# LM-008.net
KiCad netlist of a schematic drawn in Altium Designer
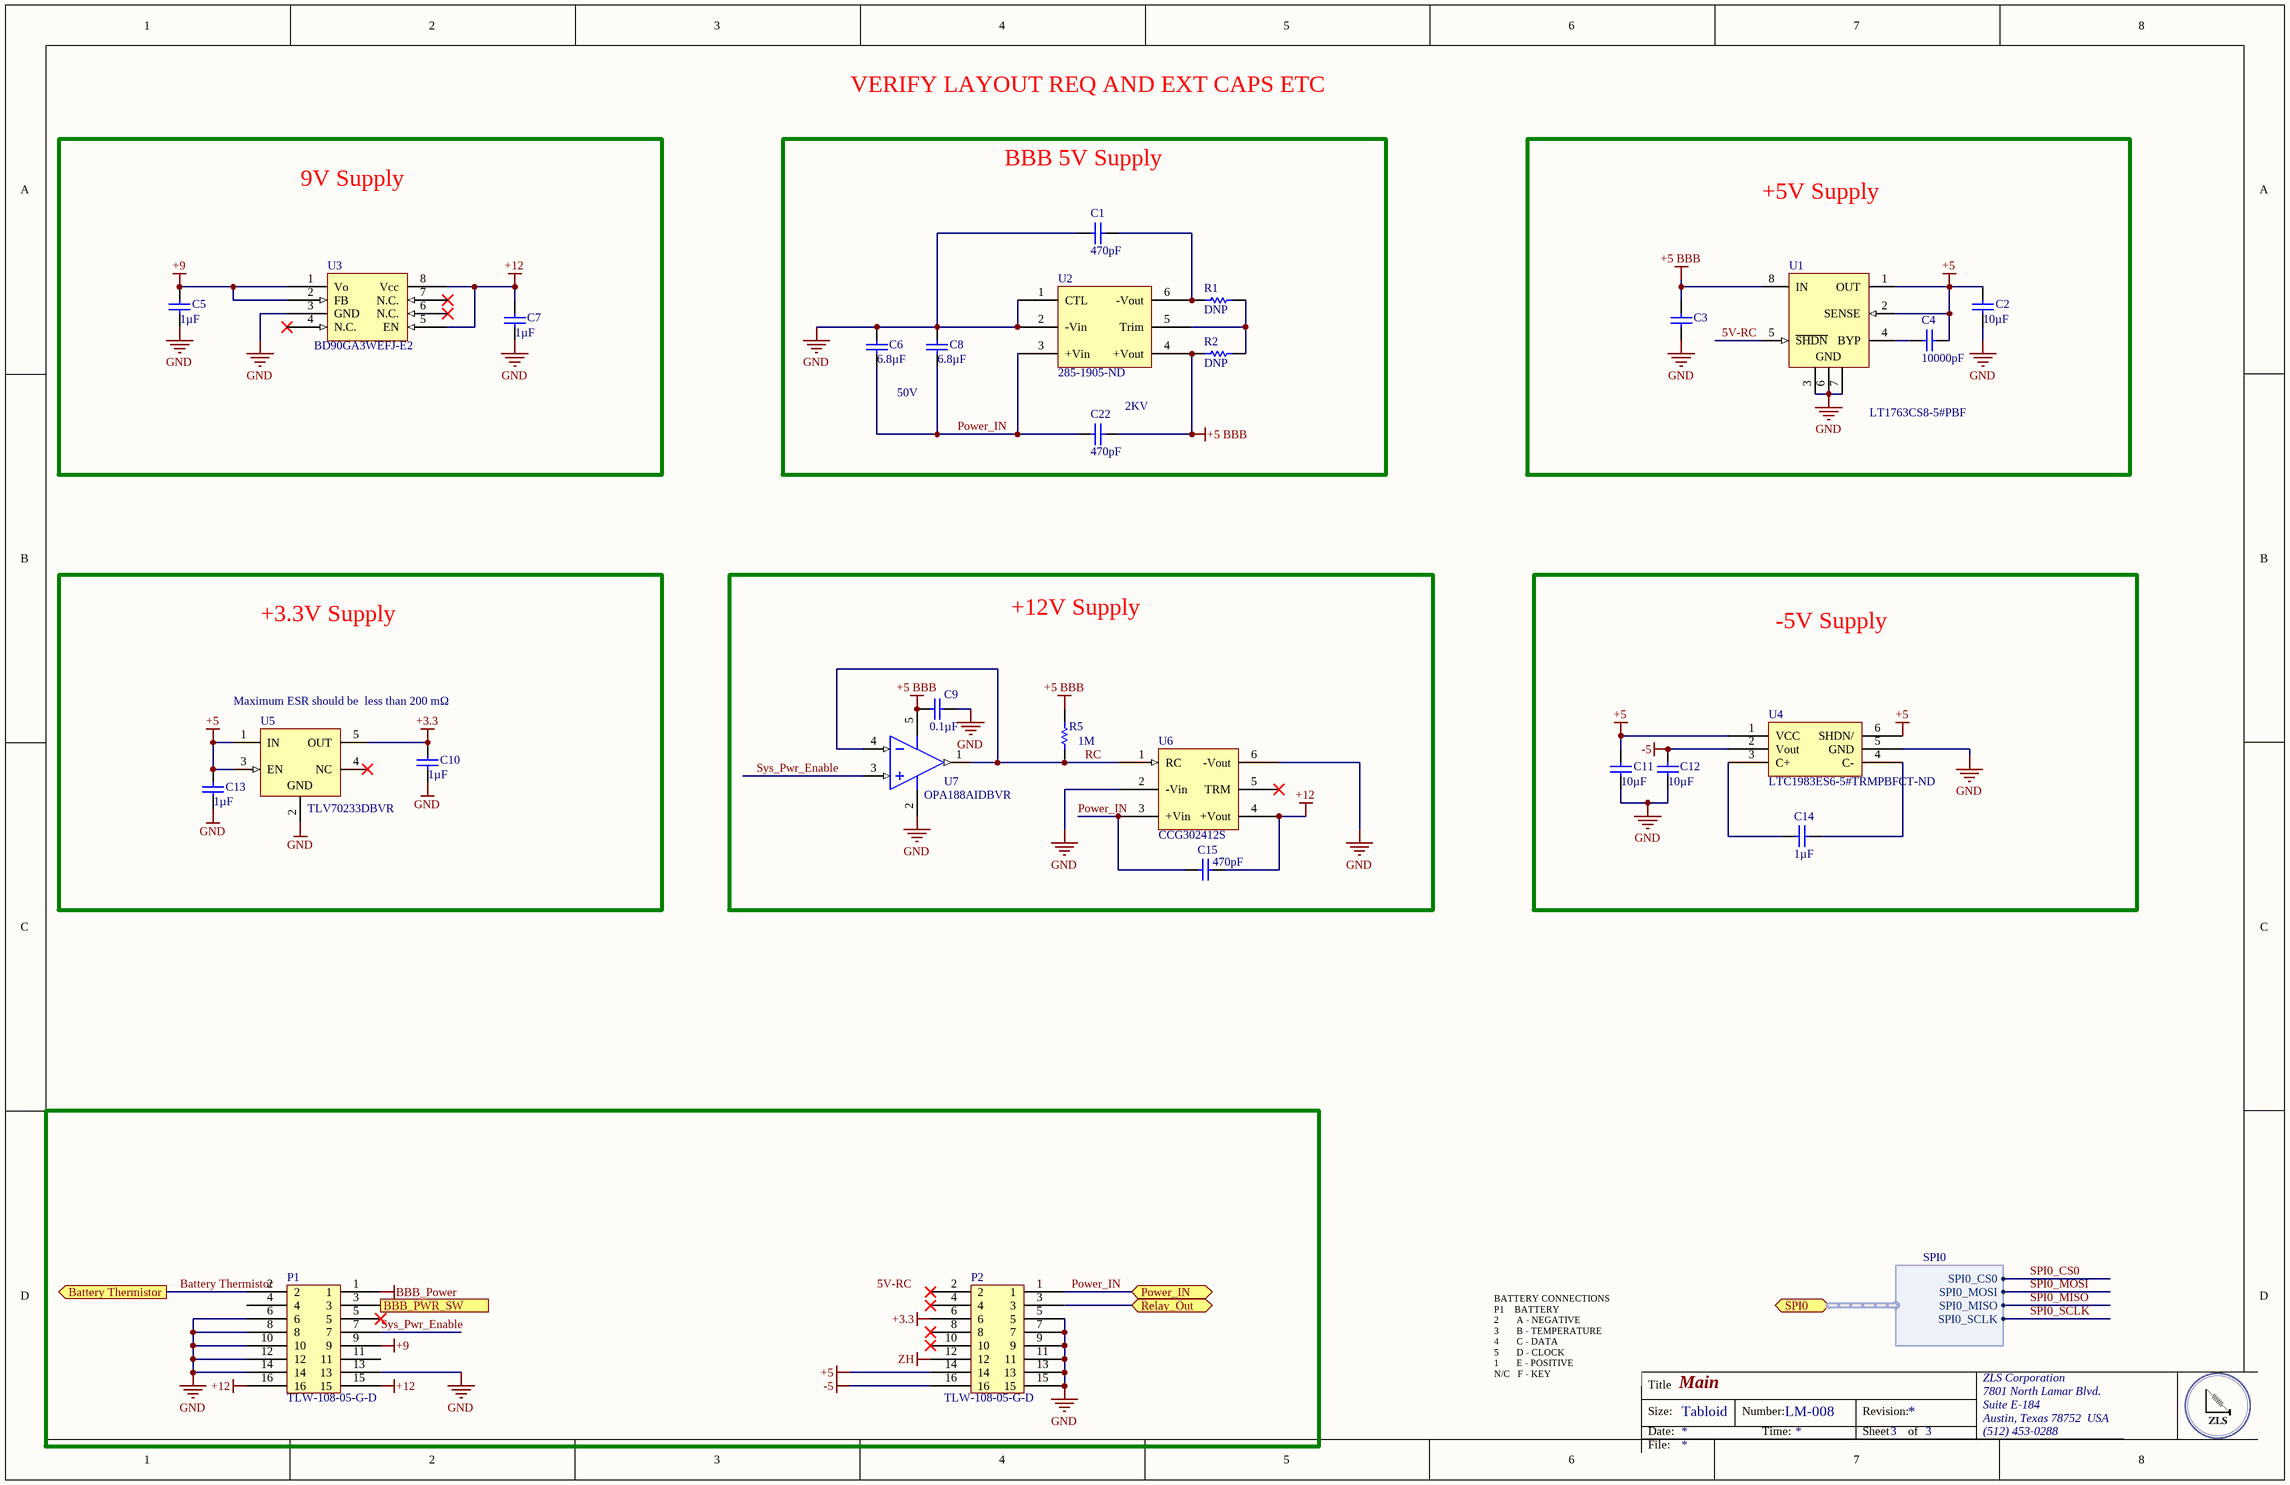
[diagram p0: LM-008.SchDoc]

(export (version "E")
  (design (tool "Eeschema 10.0.6"))
  (components
    (comp (ref "C1")
      (value "CAP CER 1UF 50V X7R 1210")
      (footprint "CAPC1206(3216)130_N")
      (fields
        (field (name "MANUFACTURER") "Murata Electronics North America")
        (field (name "MANUFACTURER PART NUMBER") "GRM32RR71H105KA01L")
        (field (name "CAPACITANCE") "470pF")
        (field (name "TOLERANCE") "±10%")
      )
      (libsource (lib "Altium Content Vault") (part "CMP-1037-04913-1"))
    )
    (comp (ref "C2")
      (value "CAP CER 1UF 50V X7R 1210")
      (footprint "CAPC1206(3216)130_N")
      (fields
        (field (name "MANUFACTURER") "Murata Electronics North America")
        (field (name "MANUFACTURER PART NUMBER") "GRM32RR71H105KA01L")
        (field (name "CAPACITANCE") "10µF")
        (field (name "TOLERANCE") "±10%")
      )
      (libsource (lib "Altium Content Vault") (part "CMP-1037-04913-1"))
    )
    (comp (ref "C3")
      (value "1uF")
      (footprint "CAPC1206(3216)130_N")
      (libsource (lib "Altium Content Vault") (part "CMP-1037-04913-1"))
    )
    (comp (ref "C4")
      (value "CAP CER 1UF 50V X7R 1210")
      (footprint "CAPC1206(3216)130_N")
      (fields
        (field (name "MANUFACTURER") "Murata Electronics North America")
        (field (name "MANUFACTURER PART NUMBER") "GRM32RR71H105KA01L")
        (field (name "CAPACITANCE") "10000pF")
        (field (name "TOLERANCE") "±10%")
      )
      (libsource (lib "Altium Content Vault") (part "CMP-1037-04913-1"))
    )
    (comp (ref "C5")
      (value "CAP CER 1UF 50V X7R 1210")
      (footprint "CAPC1206(3216)130_N")
      (fields
        (field (name "MANUFACTURER") "Murata Electronics North America")
        (field (name "MANUFACTURER PART NUMBER") "GRM32RR71H105KA01L")
        (field (name "CAPACITANCE") "1µF")
        (field (name "TOLERANCE") "±10%")
      )
      (libsource (lib "Altium Content Vault") (part "CMP-1037-04913-1"))
    )
    (comp (ref "C6")
      (value "CAP CER 1UF 50V X7R 1210")
      (footprint "CAPC1206(3216)130_N")
      (fields
        (field (name "MANUFACTURER") "Murata Electronics North America")
        (field (name "MANUFACTURER PART NUMBER") "GRM32RR71H105KA01L")
        (field (name "CAPACITANCE") "6.8µF")
        (field (name "TOLERANCE") "±10%")
      )
      (libsource (lib "Altium Content Vault") (part "CMP-1037-04913-1"))
    )
    (comp (ref "C7")
      (value "CAP CER 1UF 50V X7R 1210")
      (footprint "CAPC1206(3216)130_N")
      (fields
        (field (name "MANUFACTURER") "Murata Electronics North America")
        (field (name "MANUFACTURER PART NUMBER") "GRM32RR71H105KA01L")
        (field (name "CAPACITANCE") "1µF")
        (field (name "TOLERANCE") "±10%")
      )
      (libsource (lib "Altium Content Vault") (part "CMP-1037-04913-1"))
    )
    (comp (ref "C8")
      (value "CAP CER 1UF 50V X7R 1210")
      (footprint "CAPC1206(3216)130_N")
      (fields
        (field (name "MANUFACTURER") "Murata Electronics North America")
        (field (name "MANUFACTURER PART NUMBER") "GRM32RR71H105KA01L")
        (field (name "CAPACITANCE") "6.8µF")
        (field (name "TOLERANCE") "±10%")
      )
      (libsource (lib "Altium Content Vault") (part "CMP-1037-04913-1"))
    )
    (comp (ref "C9")
      (value "CAP CER 0.1UF 16V X7R 0805")
      (footprint "CAPC0805(2012)145_N")
      (fields
        (field (name "TOLERANCE") "±10%")
        (field (name "MANUFACTURER") "Murata Electronics North America")
        (field (name "MANUFACTURER PART NUMBER") "GRM219R71C104KA01D")
        (field (name "CAPACITANCE") "0.1µF")
      )
      (libsource (lib "Altium Content Vault") (part "CMP-1036-04795-1"))
    )
    (comp (ref "C10")
      (value "CAP CER 1UF 50V X7R 1210")
      (footprint "CAPC1206(3216)130_N")
      (fields
        (field (name "MANUFACTURER") "Murata Electronics North America")
        (field (name "MANUFACTURER PART NUMBER") "GRM32RR71H105KA01L")
        (field (name "CAPACITANCE") "1µF")
        (field (name "TOLERANCE") "±10%")
      )
      (libsource (lib "Altium Content Vault") (part "CMP-1037-04913-1"))
    )
    (comp (ref "C11")
      (value "CAP CER 1UF 50V X7R 1210")
      (footprint "CAPC1206(3216)130_N")
      (fields
        (field (name "MANUFACTURER") "Murata Electronics North America")
        (field (name "MANUFACTURER PART NUMBER") "GRM32RR71H105KA01L")
        (field (name "CAPACITANCE") "10µF")
        (field (name "TOLERANCE") "±10%")
      )
      (libsource (lib "Altium Content Vault") (part "CMP-1037-04913-1"))
    )
    (comp (ref "C12")
      (value "CAP CER 1UF 50V X7R 1210")
      (footprint "CAPC1206(3216)130_N")
      (fields
        (field (name "MANUFACTURER") "Murata Electronics North America")
        (field (name "MANUFACTURER PART NUMBER") "GRM32RR71H105KA01L")
        (field (name "CAPACITANCE") "10µF")
        (field (name "TOLERANCE") "±10%")
      )
      (libsource (lib "Altium Content Vault") (part "CMP-1037-04913-1"))
    )
    (comp (ref "C13")
      (value "CAP CER 1UF 50V X7R 1210")
      (footprint "CAPC1206(3216)130_N")
      (fields
        (field (name "MANUFACTURER") "Murata Electronics North America")
        (field (name "MANUFACTURER PART NUMBER") "GRM32RR71H105KA01L")
        (field (name "CAPACITANCE") "1µF")
        (field (name "TOLERANCE") "±10%")
      )
      (libsource (lib "Altium Content Vault") (part "CMP-1037-04913-1"))
    )
    (comp (ref "C14")
      (value "CAP CER 1UF 50V X7R 1210")
      (footprint "CAPC1206(3216)130_N")
      (fields
        (field (name "MANUFACTURER") "Murata Electronics North America")
        (field (name "MANUFACTURER PART NUMBER") "GRM32RR71H105KA01L")
        (field (name "CAPACITANCE") "1µF")
        (field (name "TOLERANCE") "±10%")
      )
      (libsource (lib "Altium Content Vault") (part "CMP-1037-04913-1"))
    )
    (comp (ref "C15")
      (value "CAP CER 470PF 3KV X7R 1812")
      (footprint "CAPC1812(4532)230_M")
      (fields
        (field (name "MANUFACTURER") "Kemet")
        (field (name "MANUFACTURER PART NUMBER") "C1812C471KHRACTU")
        (field (name "CAPACITANCE") "470pF")
        (field (name "TOLERANCE") "10%")
      )
      (libsource (lib "Altium Content Vault") (part "CMP-1040-00561-1"))
    )
    (comp (ref "C22")
      (value "CAP CER 1UF 50V X7R 1210")
      (footprint "CAPC1206(3216)130_N")
      (fields
        (field (name "MANUFACTURER") "Murata Electronics North America")
        (field (name "MANUFACTURER PART NUMBER") "GRM32RR71H105KA01L")
        (field (name "CAPACITANCE") "470pF")
        (field (name "TOLERANCE") "±10%")
      )
      (libsource (lib "Altium Content Vault") (part "CMP-1037-04913-1"))
    )
    (comp (ref "P1")
      (value "TLW-108-05-G-D")
      (footprint "TLW-108-05-G-D")
      (description "CONN HEADER .100\" 16POS DL GOLD")
      (fields
        (field (name "MANUFACTURER") "Samtec Inc.")
        (field (name "MANUFACTURER PART NUMBER") "TLW-108-05-G-D")
      )
      (libsource (lib "ZLS_Schematic_lib") (part "TLW-108-05-G-D"))
    )
    (comp (ref "P2")
      (value "TLW-108-05-G-D")
      (footprint "TLW-108-05-G-D")
      (description "CONN HEADER .100\" 16POS DL GOLD")
      (fields
        (field (name "MANUFACTURER") "Samtec Inc.")
        (field (name "MANUFACTURER PART NUMBER") "TLW-108-05-G-D")
      )
      (libsource (lib "ZLS_Schematic_lib") (part "TLW-108-05-G-D"))
    )
    (comp (ref "R1")
      (value "DNP")
      (footprint "RESC0402(1005)_L")
      (description "TBD")
      (libsource (lib "Altium Content Vault") (part "CMP-1011-00927-1"))
    )
    (comp (ref "R2")
      (value "DNP")
      (footprint "RESC0402(1005)_L")
      (description "TBD")
      (libsource (lib "Altium Content Vault") (part "CMP-1011-00927-1"))
    )
    (comp (ref "R5")
      (value "1M")
      (footprint "RESC0402(1005)_L")
      (fields (field (name "TOLERANCE") "±1%"))
      (libsource (lib "Altium Content Vault") (part "CMP-1011-00927-1"))
    )
    (comp (ref "U1")
      (value "LT1763CS8-5#PBF")
      (footprint "LT-S8-8_L")
      (fields (field (name "MANUFACTURER") "Linear Technology"))
      (libsource (lib "Altium Content Vault") (part "LT-LT1763-S8-8"))
    )
    (comp (ref "U2")
      (value "PXB15-24WS05/NT")
      (footprint "PXB15-24WS05/NT")
      (fields (field (name "SUPPLIER PART NUMBER 1") "285-1905-ND"))
      (libsource (lib "ZLS_Schematic_lib") (part "PXB15-24WS05/NT"))
    )
    (comp (ref "U3")
      (value "BD90GA3WEFJ-E2")
      (footprint "TSOP127P600X100-8N")
      (description "IC REG LDO 9V 0.3A 8HTSOP-J")
      (fields
        (field (name "MANUFACTURER") "Rohm Semiconductor")
        (field (name "MANUFACTURER PART NUMBER") "BD90GA3WEFJ-E2")
      )
      (libsource (lib "ZLS_Schematic_lib") (part "BD90GA3WEFJ-E2"))
    )
    (comp (ref "U4")
      (value "LTC1983ES6-5#TRMPBF")
      (footprint "SOT95P323X100-6N")
      (fields
        (field (name "SUPPLIER PART NUMBER 1") "LTC1983ES6-5#TRMPBFCT-ND")
        (field (name "MANUFACTURER") "Linear Technology/Analog Devices")
        (field (name "BASE PART NUMBER") "LTC1983-5")
      )
      (libsource (lib "ZLS_Schematic_lib") (part "LTC1983ES6-5#TRMPBF"))
    )
    (comp (ref "U5")
      (value "TLV70233DBVR")
      (footprint "DBV0005A_N")
      (fields (field (name "MANUFACTURER") "Texas Instruments"))
      (libsource (lib "Altium Content Vault") (part "TI-TXX7XXXX-5"))
    )
    (comp (ref "U6")
      (value "CCG302412S")
      (footprint "CCG30")
      (description "DC/DC CONVERTER 12V 2.5A PCB")
      (libsource (lib "ZLS_LIB") (part "CCG302412S"))
    )
    (comp (ref "U7")
      (value "OPA188AIDBVR")
      (footprint "DBV0005A_M")
      (fields (field (name "MANUFACTURER") "Texas Instruments"))
      (libsource (lib "Altium Content Vault") (part "CMP-0809-00005-2"))
    )
  )
  (nets
    (net (code "2") (name "+3.3") (class "Default")
      (node (ref "C10") (pin "2") (pinfunction "2_2") (pintype "passive"))
      (node (ref "P2") (pin "6") (pinfunction "6_6") (pintype "passive"))
      (node (ref "U5") (pin "5") (pinfunction "OUT_5") (pintype "power_in"))
    )
    (net (code "3") (name "+5") (class "Default")
      (node (ref "C11") (pin "2") (pinfunction "2_2") (pintype "passive"))
      (node (ref "C13") (pin "2") (pinfunction "2_2") (pintype "passive"))
      (node (ref "C2") (pin "2") (pinfunction "2_2") (pintype "passive"))
      (node (ref "C4") (pin "1") (pinfunction "1_1") (pintype "passive"))
      (node (ref "P2") (pin "14") (pinfunction "14_14") (pintype "passive"))
      (node (ref "U1") (pin "1") (pinfunction "OUT_1") (pintype "power_in"))
      (node (ref "U1") (pin "2") (pinfunction "SENSE_2") (pintype "input"))
      (node (ref "U4") (pin "1") (pinfunction "VCC_1") (pintype "passive"))
      (node (ref "U4") (pin "6") (pinfunction "SHDN/_6") (pintype "passive"))
      (node (ref "U5") (pin "1") (pinfunction "IN_1") (pintype "power_in"))
      (node (ref "U5") (pin "3") (pinfunction "EN_3") (pintype "input"))
    )
    (net (code "4") (name "+5 BBB") (class "Default")
      (node (ref "C22") (pin "1") (pinfunction "1_1") (pintype "passive"))
      (node (ref "C3") (pin "2") (pinfunction "2_2") (pintype "passive"))
      (node (ref "C9") (pin "1") (pinfunction "1_1") (pintype "passive"))
      (node (ref "R2") (pin "2") (pinfunction "2_2") (pintype "passive"))
      (node (ref "R5") (pin "2") (pinfunction "2_2") (pintype "passive"))
      (node (ref "U1") (pin "8") (pinfunction "IN_8") (pintype "power_in"))
      (node (ref "U2") (pin "4") (pinfunction "+Vout_4") (pintype "passive"))
      (node (ref "U7") (pin "5") (pinfunction "V+_5") (pintype "power_in"))
    )
    (net (code "5") (name "+9") (class "Default")
      (node (ref "C5") (pin "2") (pinfunction "2_2") (pintype "passive"))
      (node (ref "P1") (pin "9") (pinfunction "9_9") (pintype "passive"))
      (node (ref "U3") (pin "1") (pinfunction "Vo_1") (pintype "power_in"))
      (node (ref "U3") (pin "2") (pinfunction "FB_2") (pintype "input"))
    )
    (net (code "6") (name "+12") (class "Default")
      (node (ref "C15") (pin "2") (pinfunction "2_2") (pintype "passive"))
      (node (ref "C7") (pin "2") (pinfunction "2_2") (pintype "passive"))
      (node (ref "P1") (pin "15") (pinfunction "15_15") (pintype "passive"))
      (node (ref "P1") (pin "16") (pinfunction "16_16") (pintype "passive"))
      (node (ref "U3") (pin "5") (pinfunction "EN_5") (pintype "input"))
      (node (ref "U3") (pin "8") (pinfunction "Vcc_8") (pintype "power_in"))
      (node (ref "U6") (pin "4") (pinfunction "+Vout_4") (pintype "power_in"))
    )
    (net (code "7") (name "-5") (class "Default")
      (node (ref "C12") (pin "2") (pinfunction "2_2") (pintype "passive"))
      (node (ref "P2") (pin "16") (pinfunction "16_16") (pintype "passive"))
      (node (ref "U4") (pin "2") (pinfunction "Vout_2") (pintype "passive"))
    )
    (net (code "8") (name "/5V-RC") (class "Default")
      (node (ref "U1") (pin "5") (pinfunction "~{SHDN}_5") (pintype "input"))
    )
    (net (code "9") (name "/BBB_PWR_SW") (class "Default")
      (node (ref "P1") (pin "3") (pinfunction "3_3") (pintype "passive"))
    )
    (net (code "10") (name "/Battery Thermistor") (class "Default")
      (node (ref "P1") (pin "2") (pinfunction "2_2") (pintype "passive"))
    )
    (net (code "11") (name "/Power_IN") (class "Default")
      (node (ref "C15") (pin "1") (pinfunction "1_1") (pintype "passive"))
      (node (ref "C22") (pin "2") (pinfunction "2_2") (pintype "passive"))
      (node (ref "C6") (pin "1") (pinfunction "1_1") (pintype "passive"))
      (node (ref "C8") (pin "1") (pinfunction "1_1") (pintype "passive"))
      (node (ref "P2") (pin "1") (pinfunction "1_1") (pintype "passive"))
      (node (ref "U2") (pin "3") (pinfunction "+Vin_3") (pintype "passive"))
      (node (ref "U6") (pin "3") (pinfunction "+Vin_3") (pintype "passive"))
    )
    (net (code "12") (name "/RC") (class "Default")
      (node (ref "R5") (pin "1") (pinfunction "1_1") (pintype "passive"))
      (node (ref "U6") (pin "1") (pinfunction "RC_1") (pintype "input"))
      (node (ref "U7") (pin "1") (pinfunction "OUT_1") (pintype "output"))
      (node (ref "U7") (pin "4") (pinfunction "IN-_4") (pintype "input"))
    )
    (net (code "13") (name "/Relay_Out") (class "Default")
      (node (ref "P2") (pin "3") (pinfunction "3_3") (pintype "passive"))
    )
    (net (code "18") (name "/Sys_Pwr_Enable") (class "Default")
      (node (ref "P1") (pin "7") (pinfunction "7_7") (pintype "passive"))
      (node (ref "U7") (pin "3") (pinfunction "IN+_3") (pintype "input"))
    )
    (net (code "20") (name "BBB_Power") (class "Default")
      (node (ref "P1") (pin "1") (pinfunction "1_1") (pintype "passive"))
    )
    (net (code "21") (name "GND") (class "Default")
      (node (ref "C1") (pin "2") (pinfunction "2_2") (pintype "passive"))
      (node (ref "C10") (pin "1") (pinfunction "1_1") (pintype "passive"))
      (node (ref "C11") (pin "1") (pinfunction "1_1") (pintype "passive"))
      (node (ref "C12") (pin "1") (pinfunction "1_1") (pintype "passive"))
      (node (ref "C13") (pin "1") (pinfunction "1_1") (pintype "passive"))
      (node (ref "C2") (pin "1") (pinfunction "1_1") (pintype "passive"))
      (node (ref "C3") (pin "1") (pinfunction "1_1") (pintype "passive"))
      (node (ref "C5") (pin "1") (pinfunction "1_1") (pintype "passive"))
      (node (ref "C6") (pin "2") (pinfunction "2_2") (pintype "passive"))
      (node (ref "C7") (pin "1") (pinfunction "1_1") (pintype "passive"))
      (node (ref "C8") (pin "2") (pinfunction "2_2") (pintype "passive"))
      (node (ref "C9") (pin "2") (pinfunction "2_2") (pintype "passive"))
      (node (ref "P1") (pin "10") (pinfunction "10_10") (pintype "passive"))
      (node (ref "P1") (pin "12") (pinfunction "12_12") (pintype "passive"))
      (node (ref "P1") (pin "13") (pinfunction "13_13") (pintype "passive"))
      (node (ref "P1") (pin "14") (pinfunction "14_14") (pintype "passive"))
      (node (ref "P1") (pin "6") (pinfunction "6_6") (pintype "passive"))
      (node (ref "P1") (pin "8") (pinfunction "8_8") (pintype "passive"))
      (node (ref "P2") (pin "11") (pinfunction "11_11") (pintype "passive"))
      (node (ref "P2") (pin "13") (pinfunction "13_13") (pintype "passive"))
      (node (ref "P2") (pin "15") (pinfunction "15_15") (pintype "passive"))
      (node (ref "P2") (pin "5") (pinfunction "5_5") (pintype "passive"))
      (node (ref "P2") (pin "7") (pinfunction "7_7") (pintype "passive"))
      (node (ref "P2") (pin "9") (pinfunction "9_9") (pintype "passive"))
      (node (ref "U1") (pin "3") (pinfunction "GND_3") (pintype "power_in"))
      (node (ref "U1") (pin "6") (pinfunction "GND_6") (pintype "power_in"))
      (node (ref "U1") (pin "7") (pinfunction "GND_7") (pintype "power_in"))
      (node (ref "U2") (pin "1") (pinfunction "CTL_1") (pintype "passive"))
      (node (ref "U2") (pin "2") (pinfunction "-Vin_2") (pintype "passive"))
      (node (ref "U3") (pin "3") (pinfunction "GND_3") (pintype "power_in"))
      (node (ref "U4") (pin "5") (pinfunction "GND_5") (pintype "passive"))
      (node (ref "U5") (pin "2") (pinfunction "GND_2") (pintype "power_in"))
      (node (ref "U6") (pin "2") (pinfunction "-Vin_2") (pintype "power_in"))
      (node (ref "U6") (pin "6") (pinfunction "-Vout_6") (pintype "power_in"))
      (node (ref "U7") (pin "2") (pinfunction "V-_2") (pintype "power_in"))
    )
    (net (code "22") (name "Net-(U1-BYP)") (class "Default")
      (node (ref "C4") (pin "2") (pinfunction "2_2") (pintype "passive"))
      (node (ref "U1") (pin "4") (pinfunction "BYP_4") (pintype "passive"))
    )
    (net (code "23") (name "Net-(U2--Vout)") (class "Default")
      (node (ref "C1") (pin "1") (pinfunction "1_1") (pintype "passive"))
      (node (ref "R1") (pin "2") (pinfunction "2_2") (pintype "passive"))
      (node (ref "U2") (pin "6") (pinfunction "-Vout_6") (pintype "passive"))
    )
    (net (code "24") (name "Net-(U2-Trim)") (class "Default")
      (node (ref "R1") (pin "1") (pinfunction "1_1") (pintype "passive"))
      (node (ref "R2") (pin "1") (pinfunction "1_1") (pintype "passive"))
      (node (ref "U2") (pin "5") (pinfunction "Trim_5") (pintype "passive"))
    )
    (net (code "25") (name "Net-(U4-C+)") (class "Default")
      (node (ref "C14") (pin "2") (pinfunction "2_2") (pintype "passive"))
      (node (ref "U4") (pin "3") (pinfunction "C+_3") (pintype "passive"))
    )
    (net (code "26") (name "Net-(U4-C-)") (class "Default")
      (node (ref "C14") (pin "1") (pinfunction "1_1") (pintype "passive"))
      (node (ref "U4") (pin "4") (pinfunction "C-_4") (pintype "passive"))
    )
    (net (code "27") (name "ZH") (class "Default")
      (node (ref "P2") (pin "12") (pinfunction "12_12") (pintype "passive"))
    )
    (net (code "28") (name "unconnected-(P1-Pad4)") (class "Default")
      (node (ref "P1") (pin "4") (pinfunction "4_4") (pintype "passive"))
    )
    (net (code "29") (name "unconnected-(P1-Pad5)") (class "Default")
      (node (ref "P1") (pin "5") (pinfunction "5_5") (pintype "passive+no_connect"))
    )
    (net (code "30") (name "unconnected-(P1-Pad11)") (class "Default")
      (node (ref "P1") (pin "11") (pinfunction "11_11") (pintype "passive"))
    )
    (net (code "31") (name "unconnected-(P2-Pad2)") (class "Default")
      (node (ref "P2") (pin "2") (pinfunction "2_2") (pintype "passive+no_connect"))
    )
    (net (code "32") (name "unconnected-(P2-Pad4)") (class "Default")
      (node (ref "P2") (pin "4") (pinfunction "4_4") (pintype "passive+no_connect"))
    )
    (net (code "33") (name "unconnected-(P2-Pad8)") (class "Default")
      (node (ref "P2") (pin "8") (pinfunction "8_8") (pintype "passive+no_connect"))
    )
    (net (code "34") (name "unconnected-(P2-Pad10)") (class "Default")
      (node (ref "P2") (pin "10") (pinfunction "10_10") (pintype "passive+no_connect"))
    )
    (net (code "35") (name "unconnected-(U3-N.C.-Pad4)") (class "Default")
      (node (ref "U3") (pin "4") (pinfunction "N.C._4") (pintype "input+no_connect"))
    )
    (net (code "36") (name "unconnected-(U3-N.C.-Pad6)") (class "Default")
      (node (ref "U3") (pin "6") (pinfunction "N.C._6") (pintype "input+no_connect"))
    )
    (net (code "37") (name "unconnected-(U3-N.C.-Pad7)") (class "Default")
      (node (ref "U3") (pin "7") (pinfunction "N.C._7") (pintype "input+no_connect"))
    )
    (net (code "38") (name "unconnected-(U5-NC-Pad4)") (class "Default")
      (node (ref "U5") (pin "4") (pinfunction "NC_4") (pintype "passive+no_connect"))
    )
    (net (code "39") (name "unconnected-(U6-TRM-Pad5)") (class "Default")
      (node (ref "U6") (pin "5") (pinfunction "TRM_5") (pintype "passive+no_connect"))
    )
  )
)
